# DUT_Pin.net
KiCad netlist of a schematic drawn in Altium Designer
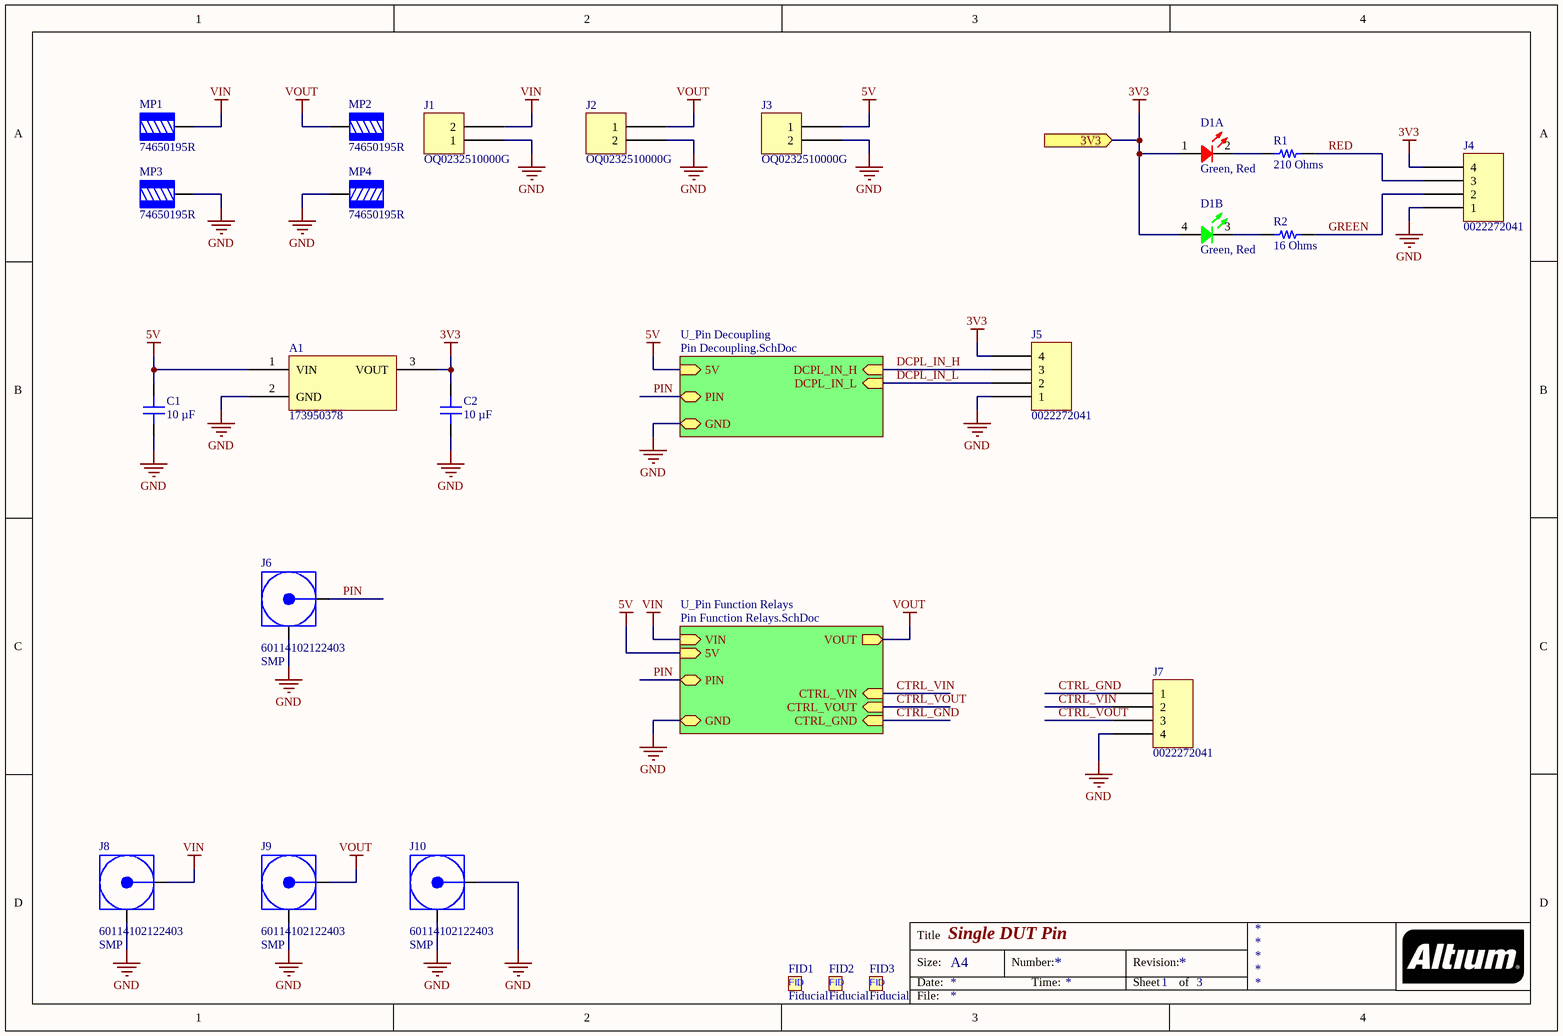
[diagram p0: DUT Pin.SchDoc]

(export (version "E")
  (design (tool "Eeschema 10.0.6"))
  (components
    (comp (ref "A1")
      (value "173950378")
      (footprint "WURTH WPME-FDSM SIP-3 173950x78")
      (description "DC DC CONVERTER 3.3V 1.65W")
      (fields (field (name "MANUFACTURER") "Würth Elektronik"))
      (libsource (lib "altiumlibrary.com") (part "WURTH MAGI3C FDSM"))
    )
    (comp (ref "C1")
      (value "10 µF")
      (footprint "CAP 1206_3216 - 0.8MM")
      (description "CAP CER 10UF 25V X7R 1206")
      (fields
        (field (name "PART NUMBER") "CL31B106KAHNNNE")
        (field (name "MANUFACTURER") "Samsung Electro-Mechanics")
      )
      (libsource (lib "altiumlibrary.com") (part "Capacitor"))
    )
    (comp (ref "C2")
      (value "10 µF")
      (footprint "CAP 1206_3216 - 0.8MM")
      (description "CAP CER 10UF 25V X7R 1206")
      (fields
        (field (name "PART NUMBER") "CL31B106KAHNNNE")
        (field (name "MANUFACTURER") "Samsung Electro-Mechanics")
      )
      (libsource (lib "altiumlibrary.com") (part "Capacitor"))
    )
    (comp (ref "D1")
      (value "Green, Red")
      (footprint "KINGBRIGHT APHBM2012SURKZGKC")
      (description "LED GREEN/RED CLEAR 4SMD")
      (fields (field (name "PART NUMBER") "APHBM2012SURKZGKC") (field (name "MANUFACTURER") "Kingbright"))
      (libsource (lib "altiumlibrary.com") (part "KINGBRIGHT APHBM2012SURKZGKC"))
    )
    (comp (ref "FID1")
      (value "Fiducial")
      (footprint "Fiducial-1mm")
      (libsource (lib "Original Circuit") (part "Fiducial"))
    )
    (comp (ref "FID2")
      (value "Fiducial")
      (footprint "Fiducial-1mm")
      (libsource (lib "Original Circuit") (part "Fiducial"))
    )
    (comp (ref "FID3")
      (value "Fiducial")
      (footprint "Fiducial-1mm")
      (libsource (lib "Original Circuit") (part "Fiducial"))
    )
    (comp (ref "J1")
      (value "OQ0232510000G")
      (footprint "FCI 06-381-2PIN")
      (description "TERM BLOCK HDR 2POS 90DEG 3.81MM")
      (fields (field (name "MANUFACTURER") "Amphenol Anytek"))
      (libsource (lib "") (part "2 Pin_1"))
    )
    (comp (ref "J2")
      (value "OQ0232510000G")
      (footprint "FCI 06-381-2PIN")
      (description "TERM BLOCK HDR 2POS 90DEG 3.81MM")
      (fields (field (name "MANUFACTURER") "Amphenol Anytek"))
      (libsource (lib "altiumlibrary.com") (part "2 Pin"))
    )
    (comp (ref "J3")
      (value "OQ0232510000G")
      (footprint "FCI 06-381-2PIN")
      (description "TERM BLOCK HDR 2POS 90DEG 3.81MM")
      (fields (field (name "MANUFACTURER") "Amphenol Anytek"))
      (libsource (lib "altiumlibrary.com") (part "2 Pin"))
    )
    (comp (ref "J4")
      (value "0022272041")
      (footprint "MOLEX KK 0022272041")
      (description "CONN HEADER VERT 4POS 2.54MM")
      (fields (field (name "MANUFACTURER") "Molex"))
      (libsource (lib "altiumlibrary.com") (part "4 Pin"))
    )
    (comp (ref "J5")
      (value "0022272041")
      (footprint "MOLEX KK 0022272041")
      (description "CONN HEADER VERT 4POS 2.54MM")
      (fields (field (name "MANUFACTURER") "Molex"))
      (libsource (lib "altiumlibrary.com") (part "4 Pin"))
    )
    (comp (ref "J6")
      (value "60114102122403")
      (footprint "WURTH SMP 60114102122403")
      (description "WR-SMP_PCB CONNECTOR_SMT PLUG")
      (fields (field (name "CONNECTOR STYLE") "SMP") (field (name "MANUFACTURER") "Würth Elektronik"))
      (libsource (lib "altiumlibrary.com") (part "COAX CONNECTOR"))
    )
    (comp (ref "J7")
      (value "0022272041")
      (footprint "MOLEX KK 0022272041")
      (description "CONN HEADER VERT 4POS 2.54MM")
      (fields (field (name "MANUFACTURER") "Molex"))
      (libsource (lib "") (part "4 Pin_1"))
    )
    (comp (ref "J8")
      (value "60114102122403")
      (footprint "WURTH SMP 60114102122403")
      (description "WR-SMP_PCB CONNECTOR_SMT PLUG")
      (fields (field (name "CONNECTOR STYLE") "SMP") (field (name "MANUFACTURER") "Würth Elektronik"))
      (libsource (lib "altiumlibrary.com") (part "COAX CONNECTOR"))
    )
    (comp (ref "J9")
      (value "60114102122403")
      (footprint "WURTH SMP 60114102122403")
      (description "WR-SMP_PCB CONNECTOR_SMT PLUG")
      (fields (field (name "CONNECTOR STYLE") "SMP") (field (name "MANUFACTURER") "Würth Elektronik"))
      (libsource (lib "altiumlibrary.com") (part "COAX CONNECTOR"))
    )
    (comp (ref "J10")
      (value "60114102122403")
      (footprint "WURTH SMP 60114102122403")
      (description "WR-SMP_PCB CONNECTOR_SMT PLUG")
      (fields (field (name "CONNECTOR STYLE") "SMP") (field (name "MANUFACTURER") "Würth Elektronik"))
      (libsource (lib "altiumlibrary.com") (part "COAX CONNECTOR"))
    )
    (comp (ref "MP1")
      (value "74650195R")
      (footprint "WURTH 74650195")
      (description "BUSH, THR CLOSEDM5, BLIND 4.0MM")
      (fields (field (name "MANUFACTURER") "Würth Elektronik"))
      (libsource (lib "altiumlibrary.com") (part "MOUNTING POINT"))
    )
    (comp (ref "MP2")
      (value "74650195R")
      (footprint "WURTH 74650195")
      (description "BUSH, THR CLOSEDM5, BLIND 4.0MM")
      (fields (field (name "MANUFACTURER") "Würth Elektronik"))
      (libsource (lib "altiumlibrary.com") (part "MOUNTING POINT"))
    )
    (comp (ref "MP3")
      (value "74650195R")
      (footprint "WURTH 74650195")
      (description "BUSH, THR CLOSEDM5, BLIND 4.0MM")
      (fields (field (name "MANUFACTURER") "Würth Elektronik"))
      (libsource (lib "altiumlibrary.com") (part "MOUNTING POINT"))
    )
    (comp (ref "MP4")
      (value "74650195R")
      (footprint "WURTH 74650195")
      (description "BUSH, THR CLOSEDM5, BLIND 4.0MM")
      (fields (field (name "MANUFACTURER") "Würth Elektronik"))
      (libsource (lib "altiumlibrary.com") (part "MOUNTING POINT"))
    )
    (comp (ref "R1")
      (value "210 Ohms")
      (footprint "RES 0603_1608")
      (description "RES 210 OHM 1% 1/10W 0603")
      (fields (field (name "PART NUMBER") "RC0603FR-07210RL") (field (name "MANUFACTURER") "Yageo"))
      (libsource (lib "altiumlibrary.com") (part "Resistor"))
    )
    (comp (ref "R2")
      (value "16 Ohms")
      (footprint "RES 0603_1608")
      (description "RES 16 OHM 1% 1/10W 0603")
      (fields (field (name "PART NUMBER") "RC0603FR-0716RL") (field (name "MANUFACTURER") "Yageo"))
      (libsource (lib "altiumlibrary.com") (part "Resistor"))
    )
  )
  (nets
    (net (code "1") (name "/CTRL_GND") (class "Default")
      (node (ref "J7") (pin "1") (pinfunction "1_1") (pintype "passive"))
    )
    (net (code "2") (name "/CTRL_VIN") (class "Default")
      (node (ref "J7") (pin "2") (pinfunction "2_2") (pintype "passive"))
    )
    (net (code "3") (name "/CTRL_VOUT") (class "Default")
      (node (ref "J7") (pin "3") (pinfunction "3_3") (pintype "passive"))
    )
    (net (code "4") (name "/DCPL_IN_H") (class "Default")
      (node (ref "J5") (pin "3") (pinfunction "3_3") (pintype "passive"))
    )
    (net (code "5") (name "/DCPL_IN_L") (class "Default")
      (node (ref "J5") (pin "2") (pinfunction "2_2") (pintype "passive"))
    )
    (net (code "6") (name "/GREEN") (class "Default")
      (node (ref "J4") (pin "2") (pinfunction "2_2") (pintype "passive"))
      (node (ref "R2") (pin "2") (pinfunction "2_2") (pintype "passive"))
    )
    (net (code "7") (name "/PIN") (class "Default")
      (node (ref "J6") (pin "S") (pinfunction "Signal_S") (pintype "passive"))
    )
    (net (code "8") (name "/RED") (class "Default")
      (node (ref "J4") (pin "3") (pinfunction "3_3") (pintype "passive"))
      (node (ref "R1") (pin "2") (pinfunction "2_2") (pintype "passive"))
    )
    (net (code "9") (name "3V3") (class "Default")
      (node (ref "A1") (pin "3") (pinfunction "VOUT_3") (pintype "passive"))
      (node (ref "C2") (pin "2") (pinfunction "2_2") (pintype "passive"))
      (node (ref "D1") (pin "1") (pinfunction "1_1") (pintype "passive"))
      (node (ref "D1") (pin "4") (pinfunction "4_4") (pintype "passive"))
      (node (ref "J4") (pin "4") (pinfunction "4_4") (pintype "passive"))
      (node (ref "J5") (pin "4") (pinfunction "4_4") (pintype "passive"))
    )
    (net (code "10") (name "5V") (class "Default")
      (node (ref "A1") (pin "1") (pinfunction "VIN_1") (pintype "passive"))
      (node (ref "C1") (pin "2") (pinfunction "2_2") (pintype "passive"))
      (node (ref "J3") (pin "1") (pinfunction "1_1") (pintype "passive"))
    )
    (net (code "11") (name "GND") (class "Default")
      (node (ref "A1") (pin "2") (pinfunction "GND_2") (pintype "passive"))
      (node (ref "C1") (pin "1") (pinfunction "1_1") (pintype "passive"))
      (node (ref "C2") (pin "1") (pinfunction "1_1") (pintype "passive"))
      (node (ref "J1") (pin "1") (pinfunction "1_1") (pintype "passive"))
      (node (ref "J10") (pin "G") (pinfunction "GND_G") (pintype "passive"))
      (node (ref "J10") (pin "S") (pinfunction "Signal_S") (pintype "passive"))
      (node (ref "J2") (pin "2") (pinfunction "2_2") (pintype "passive"))
      (node (ref "J3") (pin "2") (pinfunction "2_2") (pintype "passive"))
      (node (ref "J4") (pin "1") (pinfunction "1_1") (pintype "passive"))
      (node (ref "J5") (pin "1") (pinfunction "1_1") (pintype "passive"))
      (node (ref "J6") (pin "G") (pinfunction "GND_G") (pintype "passive"))
      (node (ref "J7") (pin "4") (pinfunction "4_4") (pintype "passive"))
      (node (ref "J8") (pin "G") (pinfunction "GND_G") (pintype "passive"))
      (node (ref "J9") (pin "G") (pinfunction "GND_G") (pintype "passive"))
      (node (ref "MP3") (pin "1") (pinfunction "1_1") (pintype "passive"))
      (node (ref "MP4") (pin "1") (pinfunction "1_1") (pintype "passive"))
    )
    (net (code "12") (name "Net-(D1-Pad2)") (class "Default")
      (node (ref "D1") (pin "2") (pinfunction "2_2") (pintype "passive"))
      (node (ref "R1") (pin "1") (pinfunction "1_1") (pintype "passive"))
    )
    (net (code "13") (name "Net-(D1-Pad3)") (class "Default")
      (node (ref "D1") (pin "3") (pinfunction "3_3") (pintype "passive"))
      (node (ref "R2") (pin "1") (pinfunction "1_1") (pintype "passive"))
    )
    (net (code "14") (name "VIN") (class "Default")
      (node (ref "J1") (pin "2") (pinfunction "2_2") (pintype "passive"))
      (node (ref "J8") (pin "S") (pinfunction "Signal_S") (pintype "passive"))
      (node (ref "MP1") (pin "1") (pinfunction "1_1") (pintype "passive"))
    )
    (net (code "15") (name "VOUT") (class "Default")
      (node (ref "J2") (pin "1") (pinfunction "1_1") (pintype "passive"))
      (node (ref "J9") (pin "S") (pinfunction "Signal_S") (pintype "passive"))
      (node (ref "MP2") (pin "1") (pinfunction "1_1") (pintype "passive"))
    )
  )
)
